# WeatherMoon.net
KiCad netlist of a schematic drawn in EAGLE
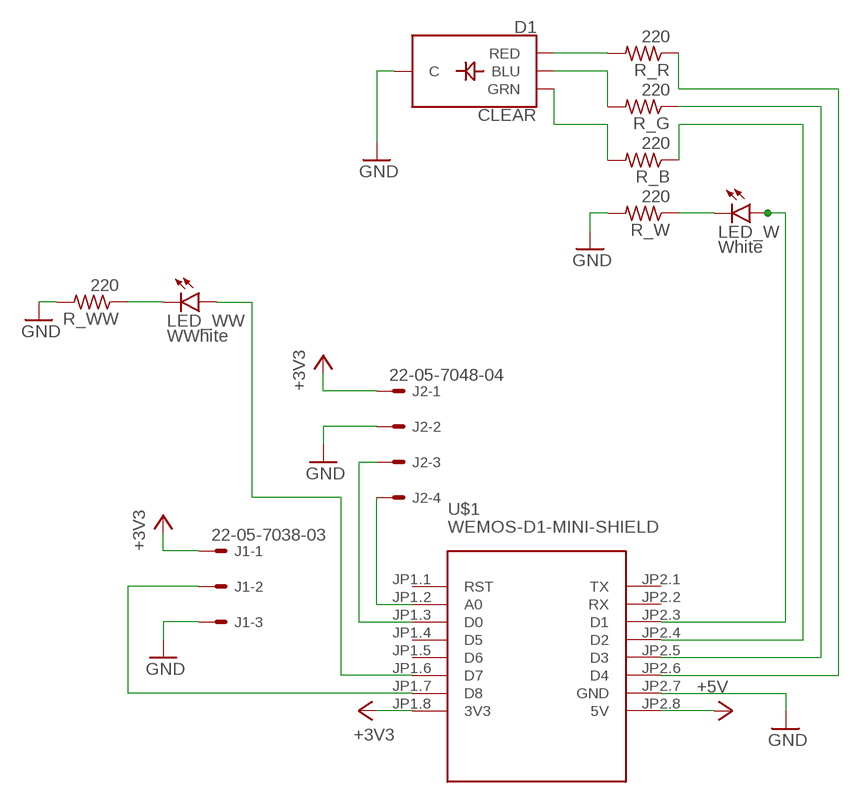
[diagram p0: schematic, sheet 1]

(export (version "E")
  (design (tool "Eeschema 10.0.6"))
  (components
    (comp (ref "D1")
      (value "CLEAR")
      (footprint "eagle-import:LED-RGB-THRU")
      (libsource (lib "eagle-import") (part "LED-RGB-CCCLEAR"))
    )
    (comp (ref "J1")
      (value "22-05-7038-03")
      (footprint "eagle-import:7395-03")
      (fields (field (name "MF") "MOLEX"))
      (libsource (lib "eagle-import") (part "22-?-0305-7038"))
    )
    (comp (ref "J2")
      (value "22-05-7048-04")
      (footprint "eagle-import:7395-04")
      (fields (field (name "MF") "MOLEX"))
      (libsource (lib "eagle-import") (part "22-?-0405-7048"))
    )
    (comp (ref "LED_W")
      (value "White")
      (footprint "eagle-import:LED5MM")
      (libsource (lib "eagle-import") (part "LED5MM"))
    )
    (comp (ref "LED_WW")
      (value "WWhite")
      (footprint "eagle-import:LED5MM")
      (libsource (lib "eagle-import") (part "LED5MM"))
    )
    (comp (ref "R_B")
      (value "220")
      (footprint "eagle-import:0204_7")
      (libsource (lib "eagle-import") (part "R-US_0204/7"))
    )
    (comp (ref "R_G")
      (value "220")
      (footprint "eagle-import:0204_7")
      (libsource (lib "eagle-import") (part "R-US_0204/7"))
    )
    (comp (ref "R_R")
      (value "220")
      (footprint "eagle-import:0204_7")
      (libsource (lib "eagle-import") (part "R-US_0204/7"))
    )
    (comp (ref "R_W")
      (value "220")
      (footprint "eagle-import:0204_7")
      (libsource (lib "eagle-import") (part "R-US_0204/7"))
    )
    (comp (ref "R_WW")
      (value "220")
      (footprint "eagle-import:0204_7")
      (libsource (lib "eagle-import") (part "R-US_0204/7"))
    )
    (comp (ref "U$1")
      (value "WEMOS-D1-MINI-SHIELD")
      (footprint "eagle-import:WEMOS-D1-MINI-SHIELD")
      (libsource (lib "eagle-import") (part "WEMOS-D1-MINI-SHIELD"))
    )
  )
  (nets
    (net (code "1") (name "+3V3") (class "Default")
      (node (ref "J1") (pin "1") (pinfunction "S_1") (pintype "passive"))
      (node (ref "J2") (pin "1") (pinfunction "S_1") (pintype "passive"))
      (node (ref "U$1") (pin "JP1.8") (pinfunction "3V3_JP1.8") (pintype "power_in"))
    )
    (net (code "2") (name "+5V") (class "Default")
      (node (ref "U$1") (pin "JP2.8") (pinfunction "5V_JP2.8") (pintype "power_in"))
    )
    (net (code "3") (name "GND") (class "Default")
      (node (ref "D1") (pin "2") (pinfunction "C_2") (pintype "bidirectional"))
      (node (ref "J1") (pin "3") (pinfunction "S_3") (pintype "passive"))
      (node (ref "J2") (pin "2") (pinfunction "S_2") (pintype "passive"))
      (node (ref "R_W") (pin "2") (pinfunction "2_2") (pintype "passive"))
      (node (ref "R_WW") (pin "2") (pinfunction "2_2") (pintype "passive"))
      (node (ref "U$1") (pin "JP2.7") (pinfunction "GND_JP2.7") (pintype "power_in"))
    )
    (net (code "4") (name "Net-(D1-BLU)") (class "Default")
      (node (ref "D1") (pin "4") (pinfunction "BLU_4") (pintype "bidirectional"))
      (node (ref "R_G") (pin "2") (pinfunction "2_2") (pintype "passive"))
    )
    (net (code "5") (name "Net-(D1-GRN)") (class "Default")
      (node (ref "D1") (pin "3") (pinfunction "GRN_3") (pintype "bidirectional"))
      (node (ref "R_B") (pin "2") (pinfunction "2_2") (pintype "passive"))
    )
    (net (code "6") (name "Net-(D1-RED)") (class "Default")
      (node (ref "D1") (pin "1") (pinfunction "RED_1") (pintype "bidirectional"))
      (node (ref "R_R") (pin "2") (pinfunction "2_2") (pintype "passive"))
    )
    (net (code "7") (name "Net-(J1B-S)") (class "Default")
      (node (ref "J1") (pin "2") (pinfunction "S_2") (pintype "passive"))
      (node (ref "U$1") (pin "JP1.7") (pinfunction "D8_JP1.7") (pintype "bidirectional"))
    )
    (net (code "8") (name "Net-(J2C-S)") (class "Default")
      (node (ref "J2") (pin "3") (pinfunction "S_3") (pintype "passive"))
      (node (ref "U$1") (pin "JP1.3") (pinfunction "D0_JP1.3") (pintype "bidirectional"))
    )
    (net (code "9") (name "Net-(J2D-S)") (class "Default")
      (node (ref "J2") (pin "4") (pinfunction "S_4") (pintype "passive"))
      (node (ref "U$1") (pin "JP1.2") (pinfunction "A0_JP1.2") (pintype "bidirectional"))
    )
    (net (code "10") (name "Net-(LED_W-C)") (class "Default")
      (node (ref "LED_W") (pin "K") (pinfunction "C_K") (pintype "passive"))
      (node (ref "R_W") (pin "1") (pinfunction "1_1") (pintype "passive"))
    )
    (net (code "11") (name "Net-(LED_WW-C)") (class "Default")
      (node (ref "LED_WW") (pin "K") (pinfunction "C_K") (pintype "passive"))
      (node (ref "R_WW") (pin "1") (pinfunction "1_1") (pintype "passive"))
    )
    (net (code "12") (name "Net-(U$1-D1)") (class "Default")
      (node (ref "LED_W") (pin "A") (pinfunction "A_A") (pintype "passive"))
      (node (ref "U$1") (pin "JP2.3") (pinfunction "D1_JP2.3") (pintype "bidirectional"))
    )
    (net (code "13") (name "Net-(U$1-D2)") (class "Default")
      (node (ref "R_B") (pin "1") (pinfunction "1_1") (pintype "passive"))
      (node (ref "U$1") (pin "JP2.4") (pinfunction "D2_JP2.4") (pintype "bidirectional"))
    )
    (net (code "14") (name "Net-(U$1-D3)") (class "Default")
      (node (ref "R_G") (pin "1") (pinfunction "1_1") (pintype "passive"))
      (node (ref "U$1") (pin "JP2.5") (pinfunction "D3_JP2.5") (pintype "bidirectional"))
    )
    (net (code "15") (name "Net-(U$1-D4)") (class "Default")
      (node (ref "R_R") (pin "1") (pinfunction "1_1") (pintype "passive"))
      (node (ref "U$1") (pin "JP2.6") (pinfunction "D4_JP2.6") (pintype "bidirectional"))
    )
    (net (code "16") (name "Net-(U$1-D7)") (class "Default")
      (node (ref "LED_WW") (pin "A") (pinfunction "A_A") (pintype "passive"))
      (node (ref "U$1") (pin "JP1.6") (pinfunction "D7_JP1.6") (pintype "bidirectional"))
    )
    (net (code "17") (name "unconnected-(U$1-D5-PadJP1.4)") (class "Default")
      (node (ref "U$1") (pin "JP1.4") (pinfunction "D5_JP1.4") (pintype "bidirectional"))
    )
    (net (code "18") (name "unconnected-(U$1-D6-PadJP1.5)") (class "Default")
      (node (ref "U$1") (pin "JP1.5") (pinfunction "D6_JP1.5") (pintype "bidirectional"))
    )
    (net (code "19") (name "unconnected-(U$1-RST-PadJP1.1)") (class "Default")
      (node (ref "U$1") (pin "JP1.1") (pinfunction "RST_JP1.1") (pintype "bidirectional"))
    )
    (net (code "20") (name "unconnected-(U$1-RX-PadJP2.2)") (class "Default")
      (node (ref "U$1") (pin "JP2.2") (pinfunction "RX_JP2.2") (pintype "bidirectional"))
    )
    (net (code "21") (name "unconnected-(U$1-TX-PadJP2.1)") (class "Default")
      (node (ref "U$1") (pin "JP2.1") (pinfunction "TX_JP2.1") (pintype "bidirectional"))
    )
  )
)
